# project1_2023-07-29.net
KiCad netlist of a schematic drawn in Altium Designer
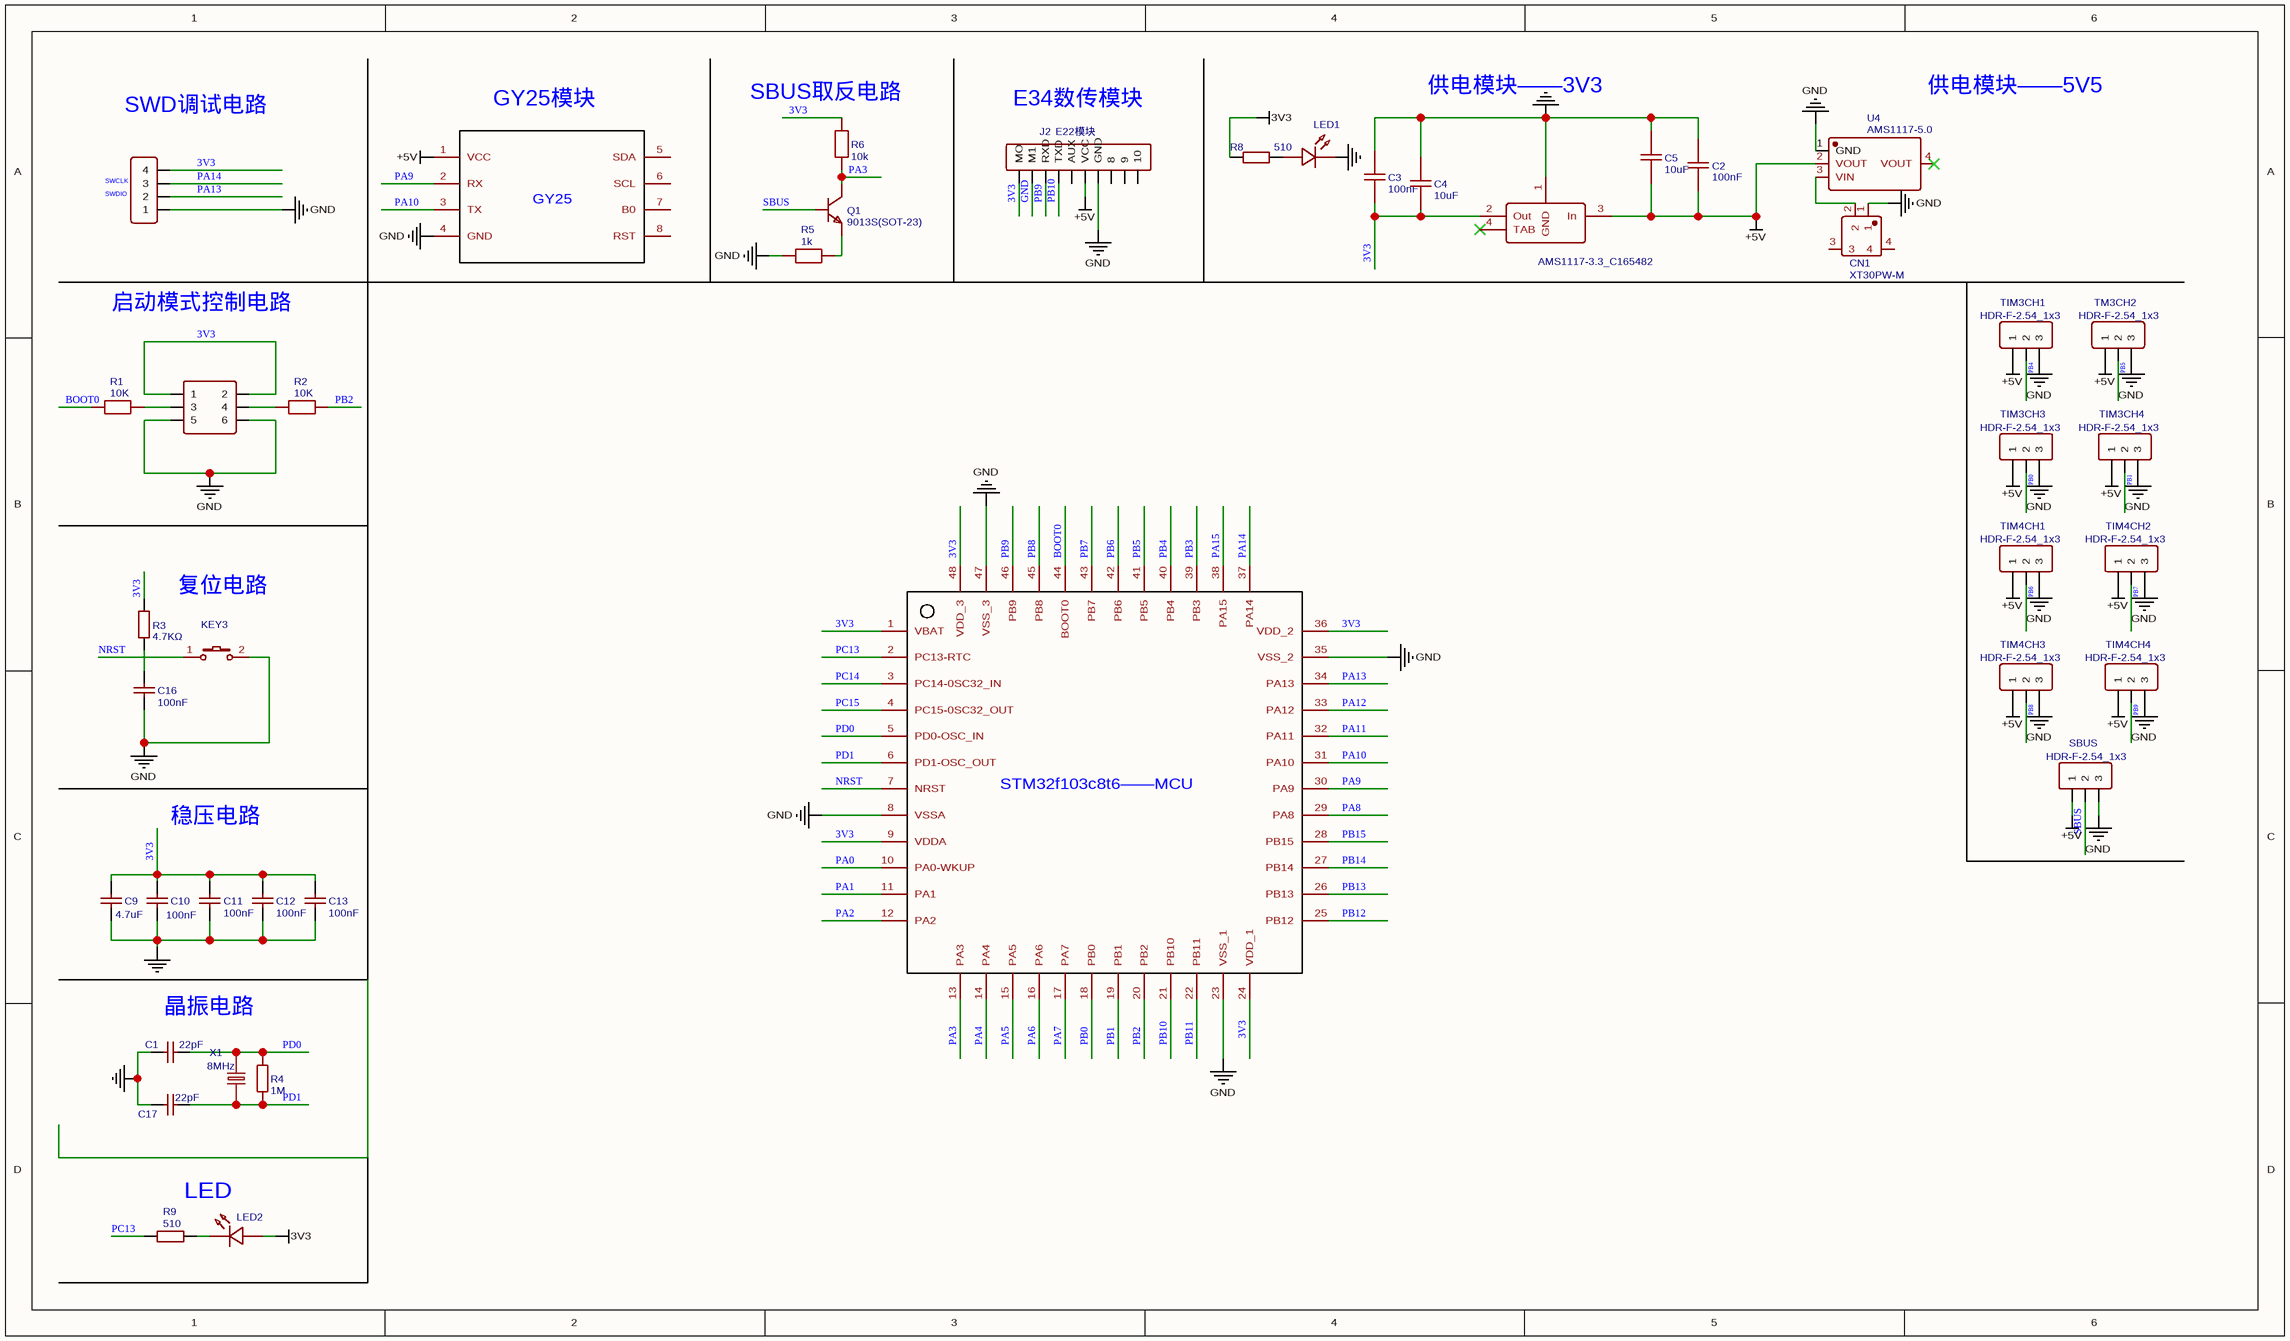
[diagram p0: project1_2023-07-29.schdoc]

(export (version "E")
  (design (tool "Eeschema 10.0.6"))
  (components
    (comp (ref "C1")
      (value "22pF")
      (fields (field (name "MANUFACTURER") "YAGEO") (field (name "MANUFACTURER PART") "CC0603JRNPO9BN220"))
      (libsource (lib "altium-import") (part "root_0_22pF_"))
    )
    (comp (ref "C2")
      (value "100nF")
      (fields (field (name "MANUFACTURER") "SAMSUNG") (field (name "MANUFACTURER PART") "CL10B104KC8NNNC"))
      (libsource (lib "") (part "root_3_100nF__1"))
    )
    (comp (ref "C3")
      (value "100nF")
      (fields (field (name "MANUFACTURER") "SAMSUNG") (field (name "MANUFACTURER PART") "CL10B104KC8NNNC"))
      (libsource (lib "") (part "root_3_100nF__1"))
    )
    (comp (ref "C4")
      (value "10uF")
      (fields
        (field (name "MANUFACTURER") "Taiyo Yuden")
        (field (name "MANUFACTURER PART") "EMK316AB7106KL-T")
        (field (name "CONTRIBUTOR") "LCSC")
      )
      (libsource (lib "altium-import") (part "root_2_10uF_"))
    )
    (comp (ref "C5")
      (value "10uF")
      (fields
        (field (name "MANUFACTURER") "Taiyo Yuden")
        (field (name "MANUFACTURER PART") "EMK316AB7106KL-T")
        (field (name "CONTRIBUTOR") "LCSC")
      )
      (libsource (lib "altium-import") (part "root_2_10uF_"))
    )
    (comp (ref "C9")
      (value "4.7uF")
      (fields
        (field (name "MANUFACTURER") "WTC")
        (field (name "MANUFACTURER PART") "0805X475K6R3")
        (field (name "CONTRIBUTOR") "LCSC")
      )
      (libsource (lib "altium-import") (part "root_1_4.7uF_"))
    )
    (comp (ref "C10")
      (value "100nF")
      (fields (field (name "MANUFACTURER PART") "CL21B104KBCNNNC") (field (name "MANUFACTURER") "SAMSUNG"))
      (libsource (lib "altium-import") (part "root_1_100nF_"))
    )
    (comp (ref "C11")
      (value "100nF")
      (fields (field (name "MANUFACTURER PART") "CL21B104KBCNNNC") (field (name "MANUFACTURER") "SAMSUNG"))
      (libsource (lib "altium-import") (part "root_1_100nF_"))
    )
    (comp (ref "C12")
      (value "100nF")
      (fields (field (name "MANUFACTURER PART") "CL21B104KBCNNNC") (field (name "MANUFACTURER") "SAMSUNG"))
      (libsource (lib "altium-import") (part "root_1_100nF_"))
    )
    (comp (ref "C13")
      (value "100nF")
      (fields (field (name "MANUFACTURER PART") "CL21B104KBCNNNC") (field (name "MANUFACTURER") "SAMSUNG"))
      (libsource (lib "altium-import") (part "root_1_100nF_"))
    )
    (comp (ref "C16")
      (value "100nF")
      (fields (field (name "MANUFACTURER PART") "CL21B104KBCNNNC") (field (name "MANUFACTURER") "SAMSUNG"))
      (libsource (lib "altium-import") (part "root_3_100nF_"))
    )
    (comp (ref "C17")
      (value "22pF")
      (fields (field (name "MANUFACTURER") "YAGEO") (field (name "MANUFACTURER PART") "CC0603JRNPO9BN220"))
      (libsource (lib "altium-import") (part "root_0_22pF_"))
    )
    (comp (ref "CN1")
      (value "XT30PW-M")
      (fields (field (name "MANUFACTURER") "Changzhou Amass Elec") (field (name "CONTRIBUTOR") "LCSC"))
      (libsource (lib "altium-import") (part "root_3_XT30PW-M_"))
    )
    (comp (ref "J1")
      (value "HDR-M-2.54_1x4")
      (fields (field (name "CONTRIBUTOR") "LCEDA_Lib"))
      (libsource (lib "altium-import") (part "root_2_HDR-M-2.54_1x4_"))
    )
    (comp (ref "J2")
      (value "E22模块")
      (fields (field (name "CONTRIBUTOR") "cherish11"))
      (libsource (lib "altium-import") (part "root_1_E22模块_"))
    )
    (comp (ref "KEY3")
      (value "K2-3.6×6.1_SMD")
      (fields (field (name "MANUFACTURER PART") "K2-1107ST-A4SW-06") (field (name "CONTRIBUTOR") "LCEDA_Lib"))
      (libsource (lib "altium-import") (part "root_0_K2-3.6×6.1_SMD_"))
    )
    (comp (ref "LED1")
      (value "LED-0805_R")
      (fields
        (field (name "MANUFACTURER") "EVERLIGHT(台湾亿光)")
        (field (name "MANUFACTURER PART") "17-21SURC/S530-A3/TR8")
        (field (name "CONTRIBUTOR") "LCEDA_Lib")
      )
      (libsource (lib "altium-import") (part "root_0_LED-0805_R_"))
    )
    (comp (ref "LED2")
      (value "LED-0805_R")
      (fields
        (field (name "MANUFACTURER") "EVERLIGHT(台湾亿光)")
        (field (name "MANUFACTURER PART") "17-21SURC/S530-A3/TR8")
        (field (name "CONTRIBUTOR") "LCEDA_Lib")
      )
      (libsource (lib "") (part "root_0_LED-0805_R__1"))
    )
    (comp (ref "P1")
      (value "HDR-IDC-2.54-2X3P")
      (fields (field (name "MANUFACTURER") "BOOMELE") (field (name "MANUFACTURER PART") "2X3 2.54mm IDC Box"))
      (libsource (lib "altium-import") (part "root_0_HDR-IDC-2.54-2X3P_"))
    )
    (comp (ref "Q1")
      (value "9013S(SOT-23)")
      (fields
        (field (name "MANUFACTURER") "KEC")
        (field (name "MANUFACTURER PART") "2n3904S-RTK/PS")
        (field (name "CONTRIBUTOR") "LCEDA_Lib")
      )
      (libsource (lib "altium-import") (part "root_0_9013S(SOT-23)_"))
    )
    (comp (ref "R1")
      (value "10K")
      (fields
        (field (name "MANUFACTURER") "Uniroyal Elec")
        (field (name "MANUFACTURER PART") "0805W8F1002T5E")
        (field (name "CONTRIBUTOR") "LCSC")
      )
      (libsource (lib "altium-import") (part "root_0_10K_"))
    )
    (comp (ref "R2")
      (value "10K")
      (fields
        (field (name "MANUFACTURER") "Uniroyal Elec")
        (field (name "MANUFACTURER PART") "0805W8F1002T5E")
        (field (name "CONTRIBUTOR") "LCSC")
      )
      (libsource (lib "altium-import") (part "root_0_10K_"))
    )
    (comp (ref "R3")
      (value "4.7KΩ")
      (fields
        (field (name "POWER") "1/10W")
        (field (name "TOLERANCE") "±5%")
        (field (name "MANUFACTURER") "UniOhm")
      )
      (libsource (lib "altium-import") (part "root_1_4.7KΩ_"))
    )
    (comp (ref "R4")
      (value "1M")
      (fields
        (field (name "MANUFACTURER") "Stackpole Elec")
        (field (name "MANUFACTURER PART") "RMCF0603FT1M00")
        (field (name "CONTRIBUTOR") "LCSC")
      )
      (libsource (lib "altium-import") (part "root_1_1M_"))
    )
    (comp (ref "R5")
      (value "1k")
      (fields (field (name "CONTRIBUTOR") "LCEDA_Lib"))
      (libsource (lib "altium-import") (part "root_2_1k_"))
    )
    (comp (ref "R6")
      (value "10k")
      (fields (field (name "CONTRIBUTOR") "LCEDA_Lib"))
      (libsource (lib "altium-import") (part "root_1_10k_"))
    )
    (comp (ref "R8")
      (value "510")
      (fields (field (name "MANUFACTURER") "LIZ") (field (name "MANUFACTURER PART") "CR0603JA0511G"))
      (libsource (lib "altium-import") (part "root_2_510_"))
    )
    (comp (ref "R9")
      (value "510")
      (fields (field (name "MANUFACTURER") "LIZ") (field (name "MANUFACTURER PART") "CR0603JA0511G"))
      (libsource (lib "altium-import") (part "root_0_510_"))
    )
    (comp (ref "SBUS")
      (value "HDR-F-2.54_1x3")
      (fields (field (name "CONTRIBUTOR") "LCEDA_Lib"))
      (libsource (lib "altium-import") (part "root_1_HDR-F-2.54_1x3_"))
    )
    (comp (ref "TIM3CH1")
      (value "HDR-F-2.54_1x3")
      (fields (field (name "CONTRIBUTOR") "LCEDA_Lib"))
      (libsource (lib "altium-import") (part "root_1_HDR-F-2.54_1x3_"))
    )
    (comp (ref "TIM3CH3")
      (value "HDR-F-2.54_1x3")
      (fields (field (name "CONTRIBUTOR") "LCEDA_Lib"))
      (libsource (lib "altium-import") (part "root_1_HDR-F-2.54_1x3_"))
    )
    (comp (ref "TIM3CH4")
      (value "HDR-F-2.54_1x3")
      (fields (field (name "CONTRIBUTOR") "LCEDA_Lib"))
      (libsource (lib "altium-import") (part "root_1_HDR-F-2.54_1x3_"))
    )
    (comp (ref "TIM4CH1")
      (value "HDR-F-2.54_1x3")
      (fields (field (name "CONTRIBUTOR") "LCEDA_Lib"))
      (libsource (lib "altium-import") (part "root_1_HDR-F-2.54_1x3_"))
    )
    (comp (ref "TIM4CH2")
      (value "HDR-F-2.54_1x3")
      (fields (field (name "CONTRIBUTOR") "LCEDA_Lib"))
      (libsource (lib "altium-import") (part "root_1_HDR-F-2.54_1x3_"))
    )
    (comp (ref "TIM4CH3")
      (value "HDR-F-2.54_1x3")
      (fields (field (name "CONTRIBUTOR") "LCEDA_Lib"))
      (libsource (lib "altium-import") (part "root_1_HDR-F-2.54_1x3_"))
    )
    (comp (ref "TIM4CH4")
      (value "HDR-F-2.54_1x3")
      (fields (field (name "CONTRIBUTOR") "LCEDA_Lib"))
      (libsource (lib "altium-import") (part "root_1_HDR-F-2.54_1x3_"))
    )
    (comp (ref "TM3CH2")
      (value "HDR-F-2.54_1x3")
      (fields (field (name "CONTRIBUTOR") "LCEDA_Lib"))
      (libsource (lib "altium-import") (part "root_1_HDR-F-2.54_1x3_"))
    )
    (comp (ref "U1")
      (value "6t6")
      (fields (field (name "CONTRIBUTOR") "wyj11"))
      (libsource (lib "altium-import") (part "root_0_6t6_"))
    )
    (comp (ref "U2")
      (value "GY25")
      (fields (field (name "CONTRIBUTOR") "wywy"))
      (libsource (lib "altium-import") (part "root_0_GY25_"))
    )
    (comp (ref "U3")
      (value "AMS1117-3.3_C165482")
      (fields
        (field (name "MANUFACTURER") "SK")
        (field (name "MANUFACTURER PART") "AMS1117-3.3")
        (field (name "CONTRIBUTOR") "LCSC")
      )
      (libsource (lib "altium-import") (part "root_2_AMS1117-3.3_C165482_"))
    )
    (comp (ref "U4")
      (value "AMS1117-5.0")
      (fields (field (name "MANUFACTURER") "AMS"))
      (libsource (lib "altium-import") (part "root_0_AMS1117-5.0_"))
    )
    (comp (ref "X1")
      (value "8MHz")
      (fields
        (field (name "MANUFACTURER") "Suzhou Liming Elec")
        (field (name "MANUFACTURER PART") "49MD-8.00-20-10-10/A")
        (field (name "CONTRIBUTOR") "LCSC")
      )
      (libsource (lib "altium-import") (part "root_1_8MHz_"))
    )
  )
  (nets
    (net (code "1") (name "+5V") (class "Default")
      (node (ref "C2") (pin "2") (pinfunction "2_2") (pintype "passive"))
      (node (ref "C5") (pin "2") (pinfunction "2_2") (pintype "passive"))
      (node (ref "J2") (pin "6") (pinfunction "VCC_6") (pintype "passive"))
      (node (ref "SBUS") (pin "1") (pinfunction "1_1") (pintype "passive"))
      (node (ref "TIM3CH1") (pin "1") (pinfunction "1_1") (pintype "passive"))
      (node (ref "TIM3CH3") (pin "1") (pinfunction "1_1") (pintype "passive"))
      (node (ref "TIM3CH4") (pin "1") (pinfunction "1_1") (pintype "passive"))
      (node (ref "TIM4CH1") (pin "1") (pinfunction "1_1") (pintype "passive"))
      (node (ref "TIM4CH2") (pin "1") (pinfunction "1_1") (pintype "passive"))
      (node (ref "TIM4CH3") (pin "1") (pinfunction "1_1") (pintype "passive"))
      (node (ref "TIM4CH4") (pin "1") (pinfunction "1_1") (pintype "passive"))
      (node (ref "TM3CH2") (pin "1") (pinfunction "1_1") (pintype "passive"))
      (node (ref "U2") (pin "1") (pinfunction "VCC_1") (pintype "passive"))
      (node (ref "U3") (pin "3") (pinfunction "In_3") (pintype "passive"))
      (node (ref "U4") (pin "2") (pinfunction "VOUT_2") (pintype "passive"))
    )
    (net (code "2") (name "/BOOT0") (class "Default")
      (node (ref "R1") (pin "1") (pinfunction "1_1") (pintype "passive"))
      (node (ref "U1") (pin "44") (pinfunction "BOOT0_44") (pintype "passive"))
    )
    (net (code "3") (name "/NRST") (class "Default")
      (node (ref "KEY3") (pin "1") (pinfunction "1_1") (pintype "passive"))
      (node (ref "U1") (pin "7") (pinfunction "NRST_7") (pintype "passive"))
    )
    (net (code "4") (name "/PA0") (class "Default")
      (node (ref "U1") (pin "10") (pinfunction "PA0-WKUP_10") (pintype "passive"))
    )
    (net (code "5") (name "/PA1") (class "Default")
      (node (ref "U1") (pin "11") (pinfunction "PA1_11") (pintype "passive"))
    )
    (net (code "6") (name "/PA2") (class "Default")
      (node (ref "U1") (pin "12") (pinfunction "PA2_12") (pintype "passive"))
    )
    (net (code "7") (name "/PA3") (class "Default")
      (node (ref "Q1") (pin "TX1") (pinfunction "C_TX1") (pintype "passive"))
      (node (ref "R6") (pin "1") (pinfunction "1_1") (pintype "passive"))
      (node (ref "U1") (pin "13") (pinfunction "PA3_13") (pintype "passive"))
    )
    (net (code "8") (name "/PA4") (class "Default")
      (node (ref "U1") (pin "14") (pinfunction "PA4_14") (pintype "passive"))
    )
    (net (code "9") (name "/PA5") (class "Default")
      (node (ref "U1") (pin "15") (pinfunction "PA5_15") (pintype "passive"))
    )
    (net (code "10") (name "/PA6") (class "Default")
      (node (ref "U1") (pin "16") (pinfunction "PA6_16") (pintype "passive"))
    )
    (net (code "11") (name "/PA7") (class "Default")
      (node (ref "U1") (pin "17") (pinfunction "PA7_17") (pintype "passive"))
    )
    (net (code "12") (name "/PA8") (class "Default")
      (node (ref "U1") (pin "29") (pinfunction "PA8_29") (pintype "passive"))
    )
    (net (code "13") (name "/PA9") (class "Default")
      (node (ref "U1") (pin "30") (pinfunction "PA9_30") (pintype "passive"))
      (node (ref "U2") (pin "2") (pinfunction "RX_2") (pintype "passive"))
    )
    (net (code "14") (name "/PA10") (class "Default")
      (node (ref "U1") (pin "31") (pinfunction "PA10_31") (pintype "passive"))
      (node (ref "U2") (pin "3") (pinfunction "TX_3") (pintype "passive"))
    )
    (net (code "15") (name "/PA11") (class "Default")
      (node (ref "U1") (pin "32") (pinfunction "PA11_32") (pintype "passive"))
    )
    (net (code "16") (name "/PA12") (class "Default")
      (node (ref "U1") (pin "33") (pinfunction "PA12_33") (pintype "passive"))
    )
    (net (code "17") (name "/PA13") (class "Default")
      (node (ref "J1") (pin "2") (pinfunction "2_2") (pintype "passive"))
      (node (ref "U1") (pin "34") (pinfunction "PA13_34") (pintype "passive"))
    )
    (net (code "18") (name "/PA14") (class "Default")
      (node (ref "J1") (pin "3") (pinfunction "3_3") (pintype "passive"))
      (node (ref "U1") (pin "37") (pinfunction "PA14_37") (pintype "passive"))
    )
    (net (code "19") (name "/PA15") (class "Default")
      (node (ref "U1") (pin "38") (pinfunction "PA15_38") (pintype "passive"))
    )
    (net (code "20") (name "/PB0") (class "Default")
      (node (ref "TIM3CH3") (pin "2") (pinfunction "2_2") (pintype "passive"))
      (node (ref "U1") (pin "18") (pinfunction "PB0_18") (pintype "passive"))
    )
    (net (code "21") (name "/PB1") (class "Default")
      (node (ref "TIM3CH4") (pin "2") (pinfunction "2_2") (pintype "passive"))
      (node (ref "U1") (pin "19") (pinfunction "PB1_19") (pintype "passive"))
    )
    (net (code "22") (name "/PB2") (class "Default")
      (node (ref "R2") (pin "2") (pinfunction "2_2") (pintype "passive"))
      (node (ref "U1") (pin "20") (pinfunction "PB2_20") (pintype "passive"))
    )
    (net (code "23") (name "/PB3") (class "Default")
      (node (ref "U1") (pin "39") (pinfunction "PB3_39") (pintype "passive"))
    )
    (net (code "24") (name "/PB4") (class "Default")
      (node (ref "TIM3CH1") (pin "2") (pinfunction "2_2") (pintype "passive"))
      (node (ref "U1") (pin "40") (pinfunction "PB4_40") (pintype "passive"))
    )
    (net (code "25") (name "/PB5") (class "Default")
      (node (ref "TM3CH2") (pin "2") (pinfunction "2_2") (pintype "passive"))
      (node (ref "U1") (pin "41") (pinfunction "PB5_41") (pintype "passive"))
    )
    (net (code "26") (name "/PB6") (class "Default")
      (node (ref "TIM4CH1") (pin "2") (pinfunction "2_2") (pintype "passive"))
      (node (ref "U1") (pin "42") (pinfunction "PB6_42") (pintype "passive"))
    )
    (net (code "27") (name "/PB7") (class "Default")
      (node (ref "TIM4CH2") (pin "2") (pinfunction "2_2") (pintype "passive"))
      (node (ref "U1") (pin "43") (pinfunction "PB7_43") (pintype "passive"))
    )
    (net (code "28") (name "/PB8") (class "Default")
      (node (ref "TIM4CH3") (pin "2") (pinfunction "2_2") (pintype "passive"))
      (node (ref "U1") (pin "45") (pinfunction "PB8_45") (pintype "passive"))
    )
    (net (code "29") (name "/PB9") (class "Default")
      (node (ref "J2") (pin "3") (pinfunction "RXD_3") (pintype "passive"))
      (node (ref "TIM4CH4") (pin "2") (pinfunction "2_2") (pintype "passive"))
      (node (ref "U1") (pin "46") (pinfunction "PB9_46") (pintype "passive"))
    )
    (net (code "30") (name "/PB10") (class "Default")
      (node (ref "J2") (pin "4") (pinfunction "TXD_4") (pintype "passive"))
      (node (ref "U1") (pin "21") (pinfunction "PB10_21") (pintype "passive"))
    )
    (net (code "31") (name "/PB11") (class "Default")
      (node (ref "U1") (pin "22") (pinfunction "PB11_22") (pintype "passive"))
    )
    (net (code "32") (name "/PB12") (class "Default")
      (node (ref "U1") (pin "25") (pinfunction "PB12_25") (pintype "passive"))
    )
    (net (code "33") (name "/PB13") (class "Default")
      (node (ref "U1") (pin "26") (pinfunction "PB13_26") (pintype "passive"))
    )
    (net (code "34") (name "/PB14") (class "Default")
      (node (ref "U1") (pin "27") (pinfunction "PB14_27") (pintype "passive"))
    )
    (net (code "35") (name "/PB15") (class "Default")
      (node (ref "U1") (pin "28") (pinfunction "PB15_28") (pintype "passive"))
    )
    (net (code "36") (name "/PC13") (class "Default")
      (node (ref "R9") (pin "1") (pinfunction "1_1") (pintype "passive"))
      (node (ref "U1") (pin "2") (pinfunction "PC13-RTC_2") (pintype "passive"))
    )
    (net (code "37") (name "/PC14") (class "Default")
      (node (ref "U1") (pin "3") (pinfunction "PC14-0SC32_IN_3") (pintype "passive"))
    )
    (net (code "38") (name "/PC15") (class "Default")
      (node (ref "U1") (pin "4") (pinfunction "PC15-0SC32_OUT_4") (pintype "passive"))
    )
    (net (code "39") (name "/PD0") (class "Default")
      (node (ref "C1") (pin "2") (pinfunction "2_2") (pintype "passive"))
      (node (ref "R4") (pin "2") (pinfunction "2_2") (pintype "passive"))
      (node (ref "U1") (pin "5") (pinfunction "PD0-OSC_IN_5") (pintype "passive"))
      (node (ref "X1") (pin "2") (pinfunction "2_2") (pintype "passive"))
    )
    (net (code "40") (name "/PD1") (class "Default")
      (node (ref "C17") (pin "2") (pinfunction "2_2") (pintype "passive"))
      (node (ref "R4") (pin "1") (pinfunction "1_1") (pintype "passive"))
      (node (ref "U1") (pin "6") (pinfunction "PD1-OSC_OUT_6") (pintype "passive"))
      (node (ref "X1") (pin "1") (pinfunction "1_1") (pintype "passive"))
    )
    (net (code "41") (name "/SBUS") (class "Default")
      (node (ref "Q1") (pin "GND") (pinfunction "B_GND") (pintype "passive"))
      (node (ref "SBUS") (pin "2") (pinfunction "2_2") (pintype "passive"))
    )
    (net (code "42") (name "3V3") (class "Default")
      (node (ref "C10") (pin "2") (pinfunction "2_2") (pintype "passive"))
      (node (ref "C11") (pin "2") (pinfunction "2_2") (pintype "passive"))
      (node (ref "C12") (pin "2") (pinfunction "2_2") (pintype "passive"))
      (node (ref "C13") (pin "2") (pinfunction "2_2") (pintype "passive"))
      (node (ref "C3") (pin "2") (pinfunction "2_2") (pintype "passive"))
      (node (ref "C4") (pin "2") (pinfunction "2_2") (pintype "passive"))
      (node (ref "C9") (pin "2") (pinfunction "2_2") (pintype "passive"))
      (node (ref "J1") (pin "4") (pinfunction "4_4") (pintype "passive"))
      (node (ref "J2") (pin "1") (pinfunction "MO_1") (pintype "passive"))
      (node (ref "LED2") (pin "1") (pinfunction "1_1") (pintype "passive"))
      (node (ref "P1") (pin "1") (pinfunction "1_1") (pintype "passive"))
      (node (ref "P1") (pin "2") (pinfunction "2_2") (pintype "passive"))
      (node (ref "R3") (pin "2") (pinfunction "2_2") (pintype "passive"))
      (node (ref "R6") (pin "2") (pinfunction "2_2") (pintype "passive"))
      (node (ref "R8") (pin "2") (pinfunction "2_2") (pintype "passive"))
      (node (ref "U1") (pin "1") (pinfunction "VBAT_1") (pintype "passive"))
      (node (ref "U1") (pin "24") (pinfunction "VDD_1_24") (pintype "passive"))
      (node (ref "U1") (pin "36") (pinfunction "VDD_2_36") (pintype "passive"))
      (node (ref "U1") (pin "48") (pinfunction "VDD_3_48") (pintype "passive"))
      (node (ref "U1") (pin "9") (pinfunction "VDDA_9") (pintype "passive"))
      (node (ref "U3") (pin "2") (pinfunction "Out_2") (pintype "passive"))
    )
    (net (code "43") (name "GND") (class "Default")
      (node (ref "C1") (pin "1") (pinfunction "1_1") (pintype "passive"))
      (node (ref "C10") (pin "1") (pinfunction "1_1") (pintype "passive"))
      (node (ref "C11") (pin "1") (pinfunction "1_1") (pintype "passive"))
      (node (ref "C12") (pin "1") (pinfunction "1_1") (pintype "passive"))
      (node (ref "C13") (pin "1") (pinfunction "1_1") (pintype "passive"))
      (node (ref "C16") (pin "2") (pinfunction "2_2") (pintype "passive"))
      (node (ref "C17") (pin "1") (pinfunction "1_1") (pintype "passive"))
      (node (ref "C2") (pin "1") (pinfunction "1_1") (pintype "passive"))
      (node (ref "C3") (pin "1") (pinfunction "1_1") (pintype "passive"))
      (node (ref "C4") (pin "1") (pinfunction "1_1") (pintype "passive"))
      (node (ref "C5") (pin "1") (pinfunction "1_1") (pintype "passive"))
      (node (ref "C9") (pin "1") (pinfunction "1_1") (pintype "passive"))
      (node (ref "CN1") (pin "1") (pinfunction "1_1") (pintype "passive"))
      (node (ref "J1") (pin "1") (pinfunction "1_1") (pintype "passive"))
      (node (ref "J2") (pin "2") (pinfunction "M1_2") (pintype "passive"))
      (node (ref "J2") (pin "7") (pinfunction "GND_7") (pintype "passive"))
      (node (ref "KEY3") (pin "2") (pinfunction "2_2") (pintype "passive"))
      (node (ref "LED1") (pin "2") (pinfunction "2_2") (pintype "passive"))
      (node (ref "P1") (pin "5") (pinfunction "5_5") (pintype "passive"))
      (node (ref "P1") (pin "6") (pinfunction "6_6") (pintype "passive"))
      (node (ref "R5") (pin "2") (pinfunction "2_2") (pintype "passive"))
      (node (ref "SBUS") (pin "3") (pinfunction "3_3") (pintype "passive"))
      (node (ref "TIM3CH1") (pin "3") (pinfunction "3_3") (pintype "passive"))
      (node (ref "TIM3CH3") (pin "3") (pinfunction "3_3") (pintype "passive"))
      (node (ref "TIM3CH4") (pin "3") (pinfunction "3_3") (pintype "passive"))
      (node (ref "TIM4CH1") (pin "3") (pinfunction "3_3") (pintype "passive"))
      (node (ref "TIM4CH2") (pin "3") (pinfunction "3_3") (pintype "passive"))
      (node (ref "TIM4CH3") (pin "3") (pinfunction "3_3") (pintype "passive"))
      (node (ref "TIM4CH4") (pin "3") (pinfunction "3_3") (pintype "passive"))
      (node (ref "TM3CH2") (pin "3") (pinfunction "3_3") (pintype "passive"))
      (node (ref "U1") (pin "23") (pinfunction "VSS_1_23") (pintype "passive"))
      (node (ref "U1") (pin "35") (pinfunction "VSS_2_35") (pintype "passive"))
      (node (ref "U1") (pin "47") (pinfunction "VSS_3_47") (pintype "passive"))
      (node (ref "U1") (pin "8") (pinfunction "VSSA_8") (pintype "passive"))
      (node (ref "U2") (pin "4") (pinfunction "GND_4") (pintype "passive"))
      (node (ref "U3") (pin "1") (pinfunction "GND_1") (pintype "passive"))
      (node (ref "U4") (pin "1") (pinfunction "GND_1") (pintype "passive"))
    )
    (net (code "44") (name "Net-(C16-Pad1)") (class "Default")
      (node (ref "C16") (pin "1") (pinfunction "1_1") (pintype "passive"))
      (node (ref "R3") (pin "1") (pinfunction "1_1") (pintype "passive"))
    )
    (net (code "45") (name "Net-(LED1-Pad1)") (class "Default")
      (node (ref "LED1") (pin "1") (pinfunction "1_1") (pintype "passive"))
      (node (ref "R8") (pin "1") (pinfunction "1_1") (pintype "passive"))
    )
    (net (code "46") (name "Net-(LED2-Pad2)") (class "Default")
      (node (ref "LED2") (pin "2") (pinfunction "2_2") (pintype "passive"))
      (node (ref "R9") (pin "2") (pinfunction "2_2") (pintype "passive"))
    )
    (net (code "47") (name "Net-(P1-Pad3)") (class "Default")
      (node (ref "P1") (pin "3") (pinfunction "3_3") (pintype "passive"))
      (node (ref "R1") (pin "2") (pinfunction "2_2") (pintype "passive"))
    )
    (net (code "48") (name "Net-(P1-Pad4)") (class "Default")
      (node (ref "P1") (pin "4") (pinfunction "4_4") (pintype "passive"))
      (node (ref "R2") (pin "1") (pinfunction "1_1") (pintype "passive"))
    )
    (net (code "49") (name "Net-(Q1-E)") (class "Default")
      (node (ref "Q1") (pin "M1") (pinfunction "E_M1") (pintype "passive"))
      (node (ref "R5") (pin "1") (pinfunction "1_1") (pintype "passive"))
    )
    (net (code "50") (name "Net-(U4-VIN)") (class "Default")
      (node (ref "CN1") (pin "2") (pinfunction "2_2") (pintype "passive"))
      (node (ref "U4") (pin "3") (pinfunction "VIN_3") (pintype "passive"))
    )
    (net (code "51") (name "unconnected-(CN1-Pad3)") (class "Default")
      (node (ref "CN1") (pin "3") (pinfunction "3_3") (pintype "passive"))
    )
    (net (code "52") (name "unconnected-(CN1-Pad4)") (class "Default")
      (node (ref "CN1") (pin "4") (pinfunction "4_4") (pintype "passive"))
    )
    (net (code "53") (name "unconnected-(J2-AUX-Pad5)") (class "Default")
      (node (ref "J2") (pin "5") (pinfunction "AUX_5") (pintype "passive"))
    )
    (net (code "54") (name "unconnected-(J2-Pad8)") (class "Default")
      (node (ref "J2") (pin "8") (pinfunction "8_8") (pintype "passive"))
    )
    (net (code "55") (name "unconnected-(J2-Pad9)") (class "Default")
      (node (ref "J2") (pin "9") (pinfunction "9_9") (pintype "passive"))
    )
    (net (code "56") (name "unconnected-(J2-Pad10)") (class "Default")
      (node (ref "J2") (pin "10") (pinfunction "10_10") (pintype "passive"))
    )
    (net (code "57") (name "unconnected-(U2-B0-Pad7)") (class "Default")
      (node (ref "U2") (pin "7") (pinfunction "B0_7") (pintype "passive"))
    )
    (net (code "58") (name "unconnected-(U2-RST-Pad8)") (class "Default")
      (node (ref "U2") (pin "8") (pinfunction "RST_8") (pintype "passive"))
    )
    (net (code "59") (name "unconnected-(U2-SCL-Pad6)") (class "Default")
      (node (ref "U2") (pin "6") (pinfunction "SCL_6") (pintype "passive"))
    )
    (net (code "60") (name "unconnected-(U2-SDA-Pad5)") (class "Default")
      (node (ref "U2") (pin "5") (pinfunction "SDA_5") (pintype "passive"))
    )
    (net (code "61") (name "unconnected-(U3-TAB-Pad4)") (class "Default")
      (node (ref "U3") (pin "4") (pinfunction "TAB_4") (pintype "passive+no_connect"))
    )
    (net (code "62") (name "unconnected-(U4-VOUT-Pad4)") (class "Default")
      (node (ref "U4") (pin "4") (pinfunction "VOUT_4") (pintype "passive+no_connect"))
    )
  )
)
